# USB.net
KiCad netlist of a schematic drawn in Altium Designer
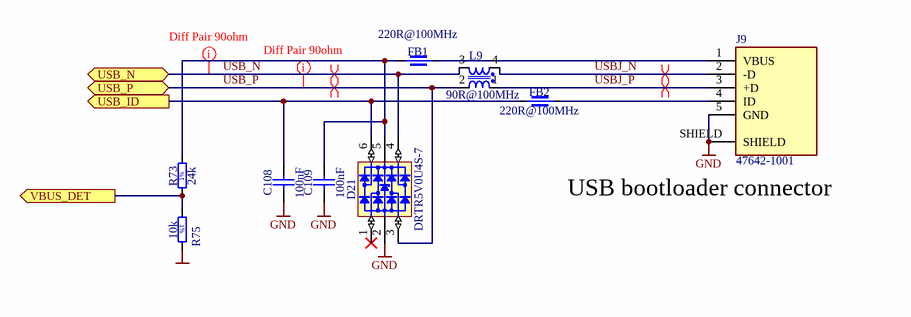
[diagram p0: USB.SchDoc]

(export (version "E")
  (design (tool "Eeschema 10.0.6"))
  (components
    (comp (ref "C108")
      (value "100nF")
      (footprint "CAPC1005X55N")
      (description "Non-polarised capacitor")
      (fields
        (field (name "PART NUMBER") "CC0402_100NF_16V_10%_X7R")
        (field (name "VOLTAGE") "16V")
        (field (name "AUTHOR") "CERN DEM JLC")
      )
      (libsource (lib "Capacitors") (part "Capacitor - non polarized"))
    )
    (comp (ref "C109")
      (value "100nF")
      (footprint "CAPC1005X55N")
      (description "Non-polarised capacitor")
      (fields
        (field (name "PART NUMBER") "CC0402_100NF_16V_10%_X7R")
        (field (name "VOLTAGE") "16V")
        (field (name "AUTHOR") "CERN DEM JLC")
      )
      (libsource (lib "Capacitors") (part "Capacitor - non polarized"))
    )
    (comp (ref "D21")
      (value "DRTR5V0U4S-7")
      (footprint "SOT65P210X110-6N")
      (description "Integrated Quad Ultra-Low Capacitance ESD Protection")
      (fields (field (name "MANUFACTURER") "DIODES") (field (name "AUTHOR") "GK"))
      (libsource (lib "Diodes") (part "D_TVS_DRTR5V0U4S-7"))
    )
    (comp (ref "FB1")
      (value "220R@100MHz")
      (footprint "INDC1005X55N")
      (fields
        (field (name "PART NUMBER") "IND0402_MURATA_BLM15HB221SN1")
        (field (name "POWER") "250mA")
        (field (name "TOLERANCE") "±25%")
        (field (name "AUTHOR") "CERN DEM JLC")
      )
      (libsource (lib "Inductors & Transformers") (part "Ferrite Bead"))
    )
    (comp (ref "FB2")
      (value "220R@100MHz")
      (footprint "INDC1005X55N")
      (fields
        (field (name "PART NUMBER") "IND0402_MURATA_BLM15HB221SN1")
        (field (name "POWER") "250mA")
        (field (name "TOLERANCE") "±25%")
        (field (name "AUTHOR") "CERN DEM JLC")
      )
      (libsource (lib "Inductors & Transformers") (part "Ferrite Bead"))
    )
    (comp (ref "J9")
      (value "47642-1001")
      (footprint "476421001")
      (description "Connector")
      (fields (field (name "MOUSER PART NUMBER") "538-47642-1001"))
      (libsource (lib "Integrated_Library_LOADER") (part "47642-1001"))
    )
    (comp (ref "L9")
      (value "90R@100MHz")
      (footprint "IND_MURATA_DLW21S")
      (description "Inductor Common Mode")
      (fields
        (field (name "PART NUMBER") "IND_MURATA_DLW21SN900SQ2L")
        (field (name "POWER") "330mA")
        (field (name "AUTHOR") "CERN DEM JLC")
      )
      (libsource (lib "Inductors & Transformers") (part "Inductor Common Mode 1Dot-2 4Dot-3"))
    )
    (comp (ref "R73")
      (value "24k")
      (footprint "RESC1608X55N")
      (description "Resistor - 1%")
      (fields
        (field (name "PART NUMBER") "R0603_24K_1%_0.1W_100PPM")
        (field (name "POWER") "0.1W")
        (field (name "AUTHOR") "CERN DEM JLC")
      )
      (libsource (lib "Resistors") (part "Resistor - 1%"))
    )
    (comp (ref "R75")
      (value "10k")
      (footprint "RESC1005X40N")
      (description "Resistor - 1%")
      (fields
        (field (name "PART NUMBER") "R0402_10K_1%_0.0625W_100PPM")
        (field (name "POWER") "0.0625W")
        (field (name "AUTHOR") "CERN DEM JLC")
      )
      (libsource (lib "Resistors") (part "Resistor - 1%"))
    )
  )
  (nets
    (net (code "1") (name "/USBJ_N") (class "Default")
      (node (ref "J9") (pin "2") (pinfunction "-D_2") (pintype "passive"))
      (node (ref "L9") (pin "4") (pinfunction "4_4") (pintype "passive"))
    )
    (net (code "2") (name "/USBJ_P") (class "Default")
      (node (ref "J9") (pin "3") (pinfunction "+D_3") (pintype "passive"))
      (node (ref "L9") (pin "1") (pinfunction "1_1") (pintype "passive"))
    )
    (net (code "3") (name "/USB_ID") (class "Default")
      (node (ref "C108") (pin "2") (pinfunction "2_2") (pintype "passive"))
      (node (ref "D21") (pin "6") (pinfunction "I/O4_6") (pintype "bidirectional"))
      (node (ref "FB2") (pin "1") (pinfunction "1_1") (pintype "passive"))
    )
    (net (code "4") (name "/USB_N") (class "Default")
      (node (ref "D21") (pin "4") (pinfunction "I/O3_4") (pintype "bidirectional"))
      (node (ref "L9") (pin "3") (pinfunction "3_3") (pintype "passive"))
    )
    (net (code "5") (name "/USB_P") (class "Default")
      (node (ref "D21") (pin "3") (pinfunction "I/O2_3") (pintype "bidirectional"))
      (node (ref "L9") (pin "2") (pinfunction "2_2") (pintype "passive"))
    )
    (net (code "6") (name "/VBUS_DET") (class "Default")
      (node (ref "R73") (pin "1") (pinfunction "1_1") (pintype "passive"))
      (node (ref "R75") (pin "1") (pinfunction "1_1") (pintype "passive"))
    )
    (net (code "7") (name "GND") (class "Default")
      (node (ref "C108") (pin "1") (pinfunction "1_1") (pintype "passive"))
      (node (ref "C109") (pin "1") (pinfunction "1_1") (pintype "passive"))
      (node (ref "D21") (pin "2") (pinfunction "GND_2") (pintype "power_in"))
      (node (ref "J9") (pin "5") (pinfunction "GND_5") (pintype "passive"))
      (node (ref "J9") (pin "SHIELD") (pinfunction "SHIELD_SHIELD") (pintype "passive"))
      (node (ref "R75") (pin "2") (pinfunction "2_2") (pintype "passive"))
    )
    (net (code "8") (name "Net-(D21-VBUS)") (class "Default")
      (node (ref "C109") (pin "2") (pinfunction "2_2") (pintype "passive"))
      (node (ref "D21") (pin "5") (pinfunction "VBUS_5") (pintype "power_in"))
      (node (ref "FB1") (pin "1") (pinfunction "1_1") (pintype "passive"))
      (node (ref "R73") (pin "2") (pinfunction "2_2") (pintype "passive"))
    )
    (net (code "9") (name "Net-(J9-ID)") (class "Default")
      (node (ref "FB2") (pin "2") (pinfunction "2_2") (pintype "passive"))
      (node (ref "J9") (pin "4") (pinfunction "ID_4") (pintype "passive"))
    )
    (net (code "10") (name "Net-(J9-VBUS)") (class "Default")
      (node (ref "FB1") (pin "2") (pinfunction "2_2") (pintype "passive"))
      (node (ref "J9") (pin "1") (pinfunction "VBUS_1") (pintype "passive"))
    )
    (net (code "11") (name "unconnected-(D21-I{slash}O1-Pad1)") (class "Default")
      (node (ref "D21") (pin "1") (pinfunction "I/O1_1") (pintype "bidirectional+no_connect"))
    )
  )
)
